# eps_adc.net
KiCad netlist of a schematic drawn in Altium Designer
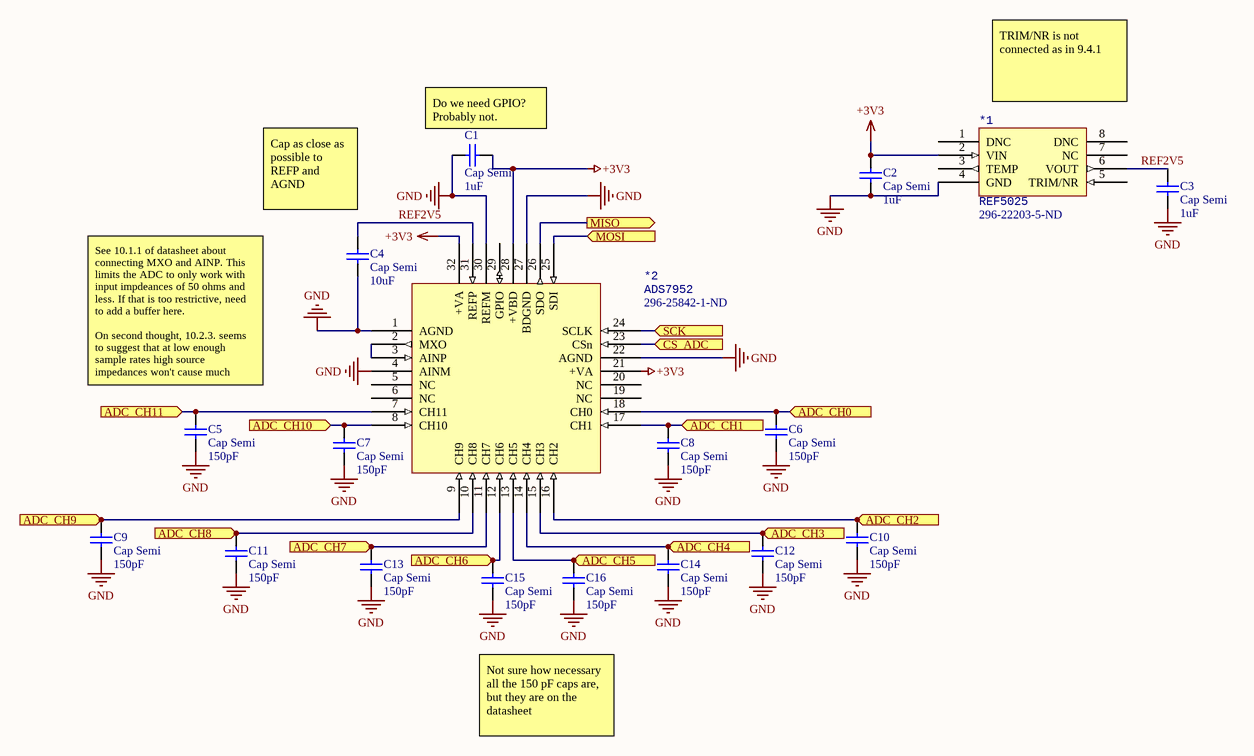
[diagram p0: eps_adc.SchDoc]

(export (version "E")
  (design (tool "Eeschema 10.0.6"))
  (components
    (comp (ref "*1")
      (value "REF5025")
      (footprint "DGK8-M")
      (description "Voltage Reference")
      (fields (field (name "SUPPLIER PART NUMBER 1") "296-22203-5-ND"))
      (libsource (lib "heron-general") (part "REF5025"))
    )
    (comp (ref "*2")
      (value "ADS7952")
      (footprint "QFN50P500X500X100-33")
      (description "12 bit, 12 channel analog-to-digital converter with SPI interface.")
      (fields (field (name "SUPPLIER PART NUMBER 1") "296-25842-1-ND"))
      (libsource (lib "ICs") (part "ADS7952"))
    )
    (comp (ref "C1")
      (value "Cap Semi")
      (footprint "1608[0603]")
      (description "Capacitor (Semiconductor SIM Model)")
      (fields (field (name "ALTIUM_VALUE") "1uF") (field (name "PUBLISHER") "Altium Limited"))
      (libsource (lib "Miscellaneous Devices") (part "Cap Semi"))
    )
    (comp (ref "C2")
      (value "Cap Semi")
      (footprint "1608[0603]")
      (description "Capacitor (Semiconductor SIM Model)")
      (fields (field (name "ALTIUM_VALUE") "1uF") (field (name "PUBLISHER") "Altium Limited"))
      (libsource (lib "Miscellaneous Devices") (part "Cap Semi"))
    )
    (comp (ref "C3")
      (value "Cap Semi")
      (footprint "1608[0603]")
      (description "Capacitor (Semiconductor SIM Model)")
      (fields (field (name "ALTIUM_VALUE") "1uF") (field (name "PUBLISHER") "Altium Limited"))
      (libsource (lib "Miscellaneous Devices") (part "Cap Semi"))
    )
    (comp (ref "C4")
      (value "Cap Semi")
      (footprint "1608[0603]")
      (description "Capacitor (Semiconductor SIM Model)")
      (fields (field (name "ALTIUM_VALUE") "10uF") (field (name "PUBLISHER") "Altium Limited"))
      (libsource (lib "Miscellaneous Devices") (part "Cap Semi"))
    )
    (comp (ref "C5")
      (value "Cap Semi")
      (footprint "1608[0603]")
      (description "Capacitor (Semiconductor SIM Model)")
      (fields (field (name "ALTIUM_VALUE") "150pF") (field (name "PUBLISHER") "Altium Limited"))
      (libsource (lib "Miscellaneous Devices") (part "Cap Semi"))
    )
    (comp (ref "C6")
      (value "Cap Semi")
      (footprint "1608[0603]")
      (description "Capacitor (Semiconductor SIM Model)")
      (fields (field (name "ALTIUM_VALUE") "150pF") (field (name "PUBLISHER") "Altium Limited"))
      (libsource (lib "Miscellaneous Devices") (part "Cap Semi"))
    )
    (comp (ref "C7")
      (value "Cap Semi")
      (footprint "1608[0603]")
      (description "Capacitor (Semiconductor SIM Model)")
      (fields (field (name "ALTIUM_VALUE") "150pF") (field (name "PUBLISHER") "Altium Limited"))
      (libsource (lib "Miscellaneous Devices") (part "Cap Semi"))
    )
    (comp (ref "C8")
      (value "Cap Semi")
      (footprint "1608[0603]")
      (description "Capacitor (Semiconductor SIM Model)")
      (fields (field (name "ALTIUM_VALUE") "150pF") (field (name "PUBLISHER") "Altium Limited"))
      (libsource (lib "Miscellaneous Devices") (part "Cap Semi"))
    )
    (comp (ref "C9")
      (value "Cap Semi")
      (footprint "1608[0603]")
      (description "Capacitor (Semiconductor SIM Model)")
      (fields (field (name "ALTIUM_VALUE") "150pF") (field (name "PUBLISHER") "Altium Limited"))
      (libsource (lib "Miscellaneous Devices") (part "Cap Semi"))
    )
    (comp (ref "C10")
      (value "Cap Semi")
      (footprint "1608[0603]")
      (description "Capacitor (Semiconductor SIM Model)")
      (fields (field (name "ALTIUM_VALUE") "150pF") (field (name "PUBLISHER") "Altium Limited"))
      (libsource (lib "Miscellaneous Devices") (part "Cap Semi"))
    )
    (comp (ref "C11")
      (value "Cap Semi")
      (footprint "1608[0603]")
      (description "Capacitor (Semiconductor SIM Model)")
      (fields (field (name "ALTIUM_VALUE") "150pF") (field (name "PUBLISHER") "Altium Limited"))
      (libsource (lib "Miscellaneous Devices") (part "Cap Semi"))
    )
    (comp (ref "C12")
      (value "Cap Semi")
      (footprint "1608[0603]")
      (description "Capacitor (Semiconductor SIM Model)")
      (fields (field (name "ALTIUM_VALUE") "150pF") (field (name "PUBLISHER") "Altium Limited"))
      (libsource (lib "Miscellaneous Devices") (part "Cap Semi"))
    )
    (comp (ref "C13")
      (value "Cap Semi")
      (footprint "1608[0603]")
      (description "Capacitor (Semiconductor SIM Model)")
      (fields (field (name "ALTIUM_VALUE") "150pF") (field (name "PUBLISHER") "Altium Limited"))
      (libsource (lib "Miscellaneous Devices") (part "Cap Semi"))
    )
    (comp (ref "C14")
      (value "Cap Semi")
      (footprint "1608[0603]")
      (description "Capacitor (Semiconductor SIM Model)")
      (fields (field (name "ALTIUM_VALUE") "150pF") (field (name "PUBLISHER") "Altium Limited"))
      (libsource (lib "Miscellaneous Devices") (part "Cap Semi"))
    )
    (comp (ref "C15")
      (value "Cap Semi")
      (footprint "1608[0603]")
      (description "Capacitor (Semiconductor SIM Model)")
      (fields (field (name "ALTIUM_VALUE") "150pF") (field (name "PUBLISHER") "Altium Limited"))
      (libsource (lib "Miscellaneous Devices") (part "Cap Semi"))
    )
    (comp (ref "C16")
      (value "Cap Semi")
      (footprint "1608[0603]")
      (description "Capacitor (Semiconductor SIM Model)")
      (fields (field (name "ALTIUM_VALUE") "150pF") (field (name "PUBLISHER") "Altium Limited"))
      (libsource (lib "Miscellaneous Devices") (part "Cap Semi"))
    )
  )
  (nets
    (net (code "1") (name "+3V3") (class "Default")
      (node (ref "*1") (pin "2") (pinfunction "VIN_2") (pintype "input"))
      (node (ref "*2") (pin "21") (pinfunction "+VA_21") (pintype "power_in"))
      (node (ref "*2") (pin "28") (pinfunction "+VBD_28") (pintype "power_in"))
      (node (ref "*2") (pin "32") (pinfunction "+VA_32") (pintype "power_in"))
      (node (ref "C1") (pin "1") (pinfunction "1_1") (pintype "passive"))
      (node (ref "C2") (pin "2") (pinfunction "2_2") (pintype "passive"))
    )
    (net (code "2") (name "/ADC_CH0") (class "Default")
      (node (ref "*2") (pin "18") (pinfunction "CH0_18") (pintype "input"))
      (node (ref "C6") (pin "1") (pinfunction "1_1") (pintype "passive"))
    )
    (net (code "3") (name "/ADC_CH1") (class "Default")
      (node (ref "*2") (pin "17") (pinfunction "CH1_17") (pintype "input"))
      (node (ref "C8") (pin "1") (pinfunction "1_1") (pintype "passive"))
    )
    (net (code "4") (name "/ADC_CH2") (class "Default")
      (node (ref "*2") (pin "16") (pinfunction "CH2_16") (pintype "input"))
      (node (ref "C10") (pin "1") (pinfunction "1_1") (pintype "passive"))
    )
    (net (code "5") (name "/ADC_CH3") (class "Default")
      (node (ref "*2") (pin "15") (pinfunction "CH3_15") (pintype "input"))
      (node (ref "C12") (pin "1") (pinfunction "1_1") (pintype "passive"))
    )
    (net (code "6") (name "/ADC_CH4") (class "Default")
      (node (ref "*2") (pin "14") (pinfunction "CH4_14") (pintype "input"))
      (node (ref "C14") (pin "1") (pinfunction "1_1") (pintype "passive"))
    )
    (net (code "7") (name "/ADC_CH5") (class "Default")
      (node (ref "*2") (pin "13") (pinfunction "CH5_13") (pintype "input"))
      (node (ref "C16") (pin "1") (pinfunction "1_1") (pintype "passive"))
    )
    (net (code "8") (name "/ADC_CH6") (class "Default")
      (node (ref "*2") (pin "12") (pinfunction "CH6_12") (pintype "input"))
      (node (ref "C15") (pin "1") (pinfunction "1_1") (pintype "passive"))
    )
    (net (code "9") (name "/ADC_CH7") (class "Default")
      (node (ref "*2") (pin "11") (pinfunction "CH7_11") (pintype "input"))
      (node (ref "C13") (pin "1") (pinfunction "1_1") (pintype "passive"))
    )
    (net (code "10") (name "/ADC_CH8") (class "Default")
      (node (ref "*2") (pin "10") (pinfunction "CH8_10") (pintype "input"))
      (node (ref "C11") (pin "1") (pinfunction "1_1") (pintype "passive"))
    )
    (net (code "11") (name "/ADC_CH9") (class "Default")
      (node (ref "*2") (pin "9") (pinfunction "CH9_9") (pintype "input"))
      (node (ref "C9") (pin "1") (pinfunction "1_1") (pintype "passive"))
    )
    (net (code "12") (name "/ADC_CH10") (class "Default")
      (node (ref "*2") (pin "8") (pinfunction "CH10_8") (pintype "input"))
      (node (ref "C7") (pin "1") (pinfunction "1_1") (pintype "passive"))
    )
    (net (code "13") (name "/ADC_CH11") (class "Default")
      (node (ref "*2") (pin "7") (pinfunction "CH11_7") (pintype "input"))
      (node (ref "C5") (pin "1") (pinfunction "1_1") (pintype "passive"))
    )
    (net (code "14") (name "/CS_ADC") (class "Default")
      (node (ref "*2") (pin "23") (pinfunction "CSn_23") (pintype "input"))
    )
    (net (code "15") (name "/MISO") (class "Default")
      (node (ref "*2") (pin "26") (pinfunction "SDO_26") (pintype "output"))
    )
    (net (code "16") (name "/MOSI") (class "Default")
      (node (ref "*2") (pin "25") (pinfunction "SDI_25") (pintype "input"))
    )
    (net (code "17") (name "/REF2V5") (class "Default")
      (node (ref "*1") (pin "6") (pinfunction "VOUT_6") (pintype "output"))
      (node (ref "*2") (pin "31") (pinfunction "REFP_31") (pintype "input"))
      (node (ref "C3") (pin "2") (pinfunction "2_2") (pintype "passive"))
      (node (ref "C4") (pin "1") (pinfunction "1_1") (pintype "passive"))
    )
    (net (code "18") (name "/SCK") (class "Default")
      (node (ref "*2") (pin "24") (pinfunction "SCLK_24") (pintype "input"))
    )
    (net (code "19") (name "GND") (class "Default")
      (node (ref "*1") (pin "4") (pinfunction "GND_4") (pintype "power_in"))
      (node (ref "*2") (pin "1") (pinfunction "AGND_1") (pintype "power_in"))
      (node (ref "*2") (pin "22") (pinfunction "AGND_22") (pintype "power_in"))
      (node (ref "*2") (pin "27") (pinfunction "BDGND_27") (pintype "power_in"))
      (node (ref "*2") (pin "30") (pinfunction "REFM_30") (pintype "power_in"))
      (node (ref "*2") (pin "4") (pinfunction "AINM_4") (pintype "power_in"))
      (node (ref "C1") (pin "2") (pinfunction "2_2") (pintype "passive"))
      (node (ref "C10") (pin "2") (pinfunction "2_2") (pintype "passive"))
      (node (ref "C11") (pin "2") (pinfunction "2_2") (pintype "passive"))
      (node (ref "C12") (pin "2") (pinfunction "2_2") (pintype "passive"))
      (node (ref "C13") (pin "2") (pinfunction "2_2") (pintype "passive"))
      (node (ref "C14") (pin "2") (pinfunction "2_2") (pintype "passive"))
      (node (ref "C15") (pin "2") (pinfunction "2_2") (pintype "passive"))
      (node (ref "C16") (pin "2") (pinfunction "2_2") (pintype "passive"))
      (node (ref "C2") (pin "1") (pinfunction "1_1") (pintype "passive"))
      (node (ref "C3") (pin "1") (pinfunction "1_1") (pintype "passive"))
      (node (ref "C4") (pin "2") (pinfunction "2_2") (pintype "passive"))
      (node (ref "C5") (pin "2") (pinfunction "2_2") (pintype "passive"))
      (node (ref "C6") (pin "2") (pinfunction "2_2") (pintype "passive"))
      (node (ref "C7") (pin "2") (pinfunction "2_2") (pintype "passive"))
      (node (ref "C8") (pin "2") (pinfunction "2_2") (pintype "passive"))
      (node (ref "C9") (pin "2") (pinfunction "2_2") (pintype "passive"))
    )
    (net (code "20") (name "Net-(*2-AINP)") (class "Default")
      (node (ref "*2") (pin "2") (pinfunction "MXO_2") (pintype "output"))
      (node (ref "*2") (pin "3") (pinfunction "AINP_3") (pintype "input"))
    )
    (net (code "21") (name "unconnected-(*1-DNC-Pad1)") (class "Default")
      (node (ref "*1") (pin "1") (pinfunction "DNC_1") (pintype "passive"))
    )
    (net (code "22") (name "unconnected-(*1-DNC-Pad8)") (class "Default")
      (node (ref "*1") (pin "8") (pinfunction "DNC_8") (pintype "passive"))
    )
    (net (code "23") (name "unconnected-(*1-NC-Pad7)") (class "Default")
      (node (ref "*1") (pin "7") (pinfunction "NC_7") (pintype "passive"))
    )
    (net (code "24") (name "unconnected-(*1-TEMP-Pad3)") (class "Default")
      (node (ref "*1") (pin "3") (pinfunction "TEMP_3") (pintype "output"))
    )
    (net (code "25") (name "unconnected-(*1-TRIM{slash}NR-Pad5)") (class "Default")
      (node (ref "*1") (pin "5") (pinfunction "TRIM/NR_5") (pintype "input"))
    )
    (net (code "26") (name "unconnected-(*2-GPIO-Pad29)") (class "Default")
      (node (ref "*2") (pin "29") (pinfunction "GPIO_29") (pintype "bidirectional"))
    )
    (net (code "27") (name "unconnected-(*2-NC-Pad5)") (class "Default")
      (node (ref "*2") (pin "5") (pinfunction "NC_5") (pintype "passive"))
    )
    (net (code "28") (name "unconnected-(*2-NC-Pad6)") (class "Default")
      (node (ref "*2") (pin "6") (pinfunction "NC_6") (pintype "passive"))
    )
    (net (code "29") (name "unconnected-(*2-NC-Pad19)") (class "Default")
      (node (ref "*2") (pin "19") (pinfunction "NC_19") (pintype "passive"))
    )
    (net (code "30") (name "unconnected-(*2-NC-Pad20)") (class "Default")
      (node (ref "*2") (pin "20") (pinfunction "NC_20") (pintype "passive"))
    )
  )
)
